# bigmuff.net
KiCad netlist of a schematic drawn in EAGLE
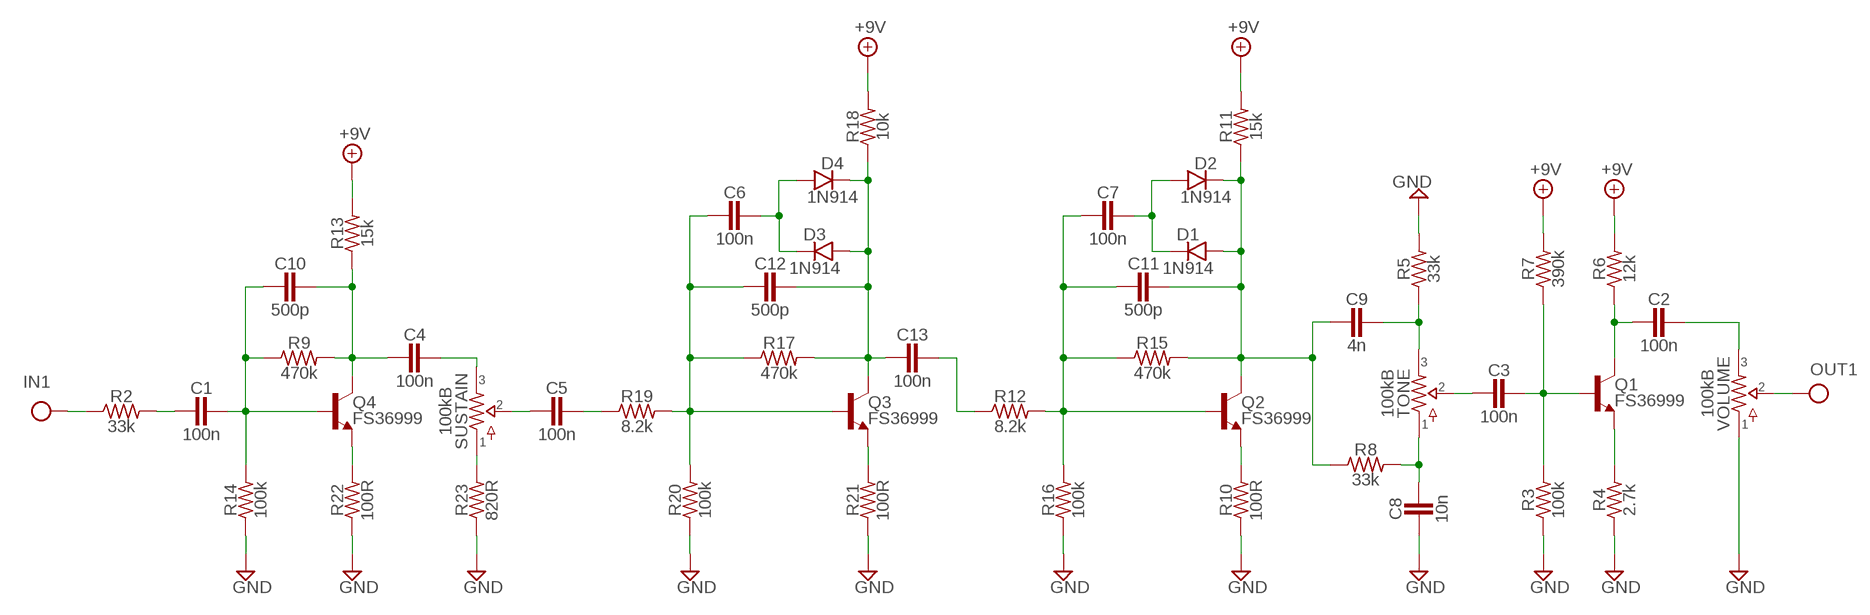
[diagram p0: schematic, sheet 1]

(export (version "E")
  (design (tool "Eeschema 10.0.6"))
  (components
    (comp (ref "C1")
      (value "100n")
      (footprint "eagle-import:BOX_SMALL")
      (libsource (lib "eagle-import") (part "CER/FILMBOX.1"))
    )
    (comp (ref "C2")
      (value "100n")
      (footprint "eagle-import:BOX_SMALL")
      (libsource (lib "eagle-import") (part "CER/FILMBOX.1"))
    )
    (comp (ref "C3")
      (value "100n")
      (footprint "eagle-import:BOX_SMALL")
      (libsource (lib "eagle-import") (part "CER/FILMBOX.1"))
    )
    (comp (ref "C4")
      (value "100n")
      (footprint "eagle-import:BOX_SMALL")
      (libsource (lib "eagle-import") (part "CER/FILMBOX.1"))
    )
    (comp (ref "C5")
      (value "100n")
      (footprint "eagle-import:BOX_SMALL")
      (libsource (lib "eagle-import") (part "CER/FILMBOX.1"))
    )
    (comp (ref "C6")
      (value "100n")
      (footprint "eagle-import:BOX_SMALL")
      (libsource (lib "eagle-import") (part "CER/FILMBOX.1"))
    )
    (comp (ref "C7")
      (value "100n")
      (footprint "eagle-import:BOX_SMALL")
      (libsource (lib "eagle-import") (part "CER/FILMBOX.1"))
    )
    (comp (ref "C8")
      (value "10n")
      (footprint "eagle-import:BOX_SMALL")
      (libsource (lib "eagle-import") (part "CER/FILMBOX.1"))
    )
    (comp (ref "C9")
      (value "4n")
      (footprint "eagle-import:BOX_SMALL")
      (libsource (lib "eagle-import") (part "CER/FILMBOX.1"))
    )
    (comp (ref "C10")
      (value "500p")
      (footprint "eagle-import:BOX_SMALL")
      (libsource (lib "eagle-import") (part "CER/FILMBOX.1"))
    )
    (comp (ref "C11")
      (value "500p")
      (footprint "eagle-import:BOX_SMALL")
      (libsource (lib "eagle-import") (part "CER/FILMBOX.1"))
    )
    (comp (ref "C12")
      (value "500p")
      (footprint "eagle-import:BOX_SMALL")
      (libsource (lib "eagle-import") (part "CER/FILMBOX.1"))
    )
    (comp (ref "C13")
      (value "100n")
      (footprint "eagle-import:BOX_SMALL")
      (libsource (lib "eagle-import") (part "CER/FILMBOX.1"))
    )
    (comp (ref "D1")
      (value "1N914")
      (footprint "eagle-import:DO41-2")
      (libsource (lib "eagle-import") (part "DO41.2"))
    )
    (comp (ref "D2")
      (value "1N914")
      (footprint "eagle-import:DO41-2")
      (libsource (lib "eagle-import") (part "DO41.2"))
    )
    (comp (ref "D3")
      (value "1N914")
      (footprint "eagle-import:DO41-2")
      (libsource (lib "eagle-import") (part "DO41.2"))
    )
    (comp (ref "D4")
      (value "1N914")
      (footprint "eagle-import:DO41-2")
      (libsource (lib "eagle-import") (part "DO41.2"))
    )
    (comp (ref "Q1")
      (value "FS36999")
      (footprint "eagle-import:TO92-")
      (libsource (lib "eagle-import") (part "2N5088"))
    )
    (comp (ref "Q2")
      (value "FS36999")
      (footprint "eagle-import:TO92-")
      (libsource (lib "eagle-import") (part "2N5088"))
    )
    (comp (ref "Q3")
      (value "FS36999")
      (footprint "eagle-import:TO92-")
      (libsource (lib "eagle-import") (part "2N5088"))
    )
    (comp (ref "Q4")
      (value "FS36999")
      (footprint "eagle-import:TO92-")
      (libsource (lib "eagle-import") (part "2N5088"))
    )
    (comp (ref "R2")
      (value "33k")
      (footprint "eagle-import:R0207_3")
      (libsource (lib "eagle-import") (part "R_.3B"))
    )
    (comp (ref "R3")
      (value "100k")
      (footprint "eagle-import:R0207_3")
      (libsource (lib "eagle-import") (part "R_.3B"))
    )
    (comp (ref "R4")
      (value "2.7k")
      (footprint "eagle-import:R0207_3")
      (libsource (lib "eagle-import") (part "R_.3B"))
    )
    (comp (ref "R5")
      (value "33k")
      (footprint "eagle-import:R0207_3")
      (libsource (lib "eagle-import") (part "R_.3B"))
    )
    (comp (ref "R6")
      (value "12k")
      (footprint "eagle-import:R0207_3")
      (libsource (lib "eagle-import") (part "R_.3B"))
    )
    (comp (ref "R7")
      (value "390k")
      (footprint "eagle-import:R0207_3")
      (libsource (lib "eagle-import") (part "R_.3B"))
    )
    (comp (ref "R8")
      (value "33k")
      (footprint "eagle-import:R0207_3")
      (libsource (lib "eagle-import") (part "R_.3B"))
    )
    (comp (ref "R9")
      (value "470k")
      (footprint "eagle-import:R0207_3")
      (libsource (lib "eagle-import") (part "R_.3B"))
    )
    (comp (ref "R10")
      (value "100R")
      (footprint "eagle-import:R0207_3")
      (libsource (lib "eagle-import") (part "R_.3B"))
    )
    (comp (ref "R11")
      (value "15k")
      (footprint "eagle-import:R0207_3")
      (libsource (lib "eagle-import") (part "R_.3B"))
    )
    (comp (ref "R12")
      (value "8.2k")
      (footprint "eagle-import:R0207_3")
      (libsource (lib "eagle-import") (part "R_.3B"))
    )
    (comp (ref "R13")
      (value "15k")
      (footprint "eagle-import:R0207_3")
      (libsource (lib "eagle-import") (part "R_.3B"))
    )
    (comp (ref "R14")
      (value "100k")
      (footprint "eagle-import:R0207_3")
      (libsource (lib "eagle-import") (part "R_.3B"))
    )
    (comp (ref "R15")
      (value "470k")
      (footprint "eagle-import:R0207_3")
      (libsource (lib "eagle-import") (part "R_.3B"))
    )
    (comp (ref "R16")
      (value "100k")
      (footprint "eagle-import:R0207_3")
      (libsource (lib "eagle-import") (part "R_.3B"))
    )
    (comp (ref "R17")
      (value "470k")
      (footprint "eagle-import:R0207_3")
      (libsource (lib "eagle-import") (part "R_.3B"))
    )
    (comp (ref "R18")
      (value "10k")
      (footprint "eagle-import:R0207_3")
      (libsource (lib "eagle-import") (part "R_.3B"))
    )
    (comp (ref "R19")
      (value "8.2k")
      (footprint "eagle-import:R0207_3")
      (libsource (lib "eagle-import") (part "R_.3B"))
    )
    (comp (ref "R20")
      (value "100k")
      (footprint "eagle-import:R0207_3")
      (libsource (lib "eagle-import") (part "R_.3B"))
    )
    (comp (ref "R21")
      (value "100R")
      (footprint "eagle-import:R0207_3")
      (libsource (lib "eagle-import") (part "R_.3B"))
    )
    (comp (ref "R22")
      (value "100R")
      (footprint "eagle-import:R0207_3")
      (libsource (lib "eagle-import") (part "R_.3B"))
    )
    (comp (ref "R23")
      (value "820R")
      (footprint "eagle-import:R0207_3")
      (libsource (lib "eagle-import") (part "R_.3B"))
    )
    (comp (ref "SUSTAIN")
      (value "100kB")
      (footprint "eagle-import:16MM")
      (libsource (lib "eagle-import") (part "POTS16MM"))
    )
    (comp (ref "TONE")
      (value "100kB")
      (footprint "eagle-import:16MM")
      (libsource (lib "eagle-import") (part "POTS16MM"))
    )
    (comp (ref "VOLUME")
      (value "100kB")
      (footprint "eagle-import:16MM")
      (libsource (lib "eagle-import") (part "POTS16MM"))
    )
  )
  (nets
    (net (code "1") (name "+9V") (class "Default")
      (node (ref "R11") (pin "2") (pinfunction "2_2") (pintype "passive"))
      (node (ref "R13") (pin "2") (pinfunction "2_2") (pintype "passive"))
      (node (ref "R18") (pin "2") (pinfunction "2_2") (pintype "passive"))
      (node (ref "R6") (pin "2") (pinfunction "2_2") (pintype "passive"))
      (node (ref "R7") (pin "2") (pinfunction "2_2") (pintype "passive"))
    )
    (net (code "2") (name "GND") (class "Default")
      (node (ref "C8") (pin "2") (pinfunction "2_2") (pintype "passive"))
      (node (ref "R10") (pin "1") (pinfunction "1_1") (pintype "passive"))
      (node (ref "R14") (pin "1") (pinfunction "1_1") (pintype "passive"))
      (node (ref "R16") (pin "1") (pinfunction "1_1") (pintype "passive"))
      (node (ref "R20") (pin "1") (pinfunction "1_1") (pintype "passive"))
      (node (ref "R21") (pin "1") (pinfunction "1_1") (pintype "passive"))
      (node (ref "R22") (pin "1") (pinfunction "1_1") (pintype "passive"))
      (node (ref "R23") (pin "1") (pinfunction "1_1") (pintype "passive"))
      (node (ref "R3") (pin "1") (pinfunction "1_1") (pintype "passive"))
      (node (ref "R4") (pin "1") (pinfunction "1_1") (pintype "passive"))
      (node (ref "R5") (pin "2") (pinfunction "2_2") (pintype "passive"))
      (node (ref "VOLUME") (pin "1") (pinfunction "1_1") (pintype "passive"))
    )
    (net (code "3") (name "IN") (class "Default")
      (node (ref "R2") (pin "1") (pinfunction "1_1") (pintype "passive"))
    )
    (net (code "4") (name "Net-(C1-Pad2)") (class "Default")
      (node (ref "C1") (pin "2") (pinfunction "2_2") (pintype "passive"))
      (node (ref "R2") (pin "2") (pinfunction "2_2") (pintype "passive"))
    )
    (net (code "5") (name "Net-(C2-Pad1)") (class "Default")
      (node (ref "C2") (pin "1") (pinfunction "1_1") (pintype "passive"))
      (node (ref "VOLUME") (pin "3") (pinfunction "3_3") (pintype "passive"))
    )
    (net (code "6") (name "Net-(C3-Pad2)") (class "Default")
      (node (ref "C3") (pin "2") (pinfunction "2_2") (pintype "passive"))
      (node (ref "TONE") (pin "2") (pinfunction "2_2") (pintype "passive"))
    )
    (net (code "7") (name "Net-(C4-Pad1)") (class "Default")
      (node (ref "C4") (pin "1") (pinfunction "1_1") (pintype "passive"))
      (node (ref "SUSTAIN") (pin "3") (pinfunction "3_3") (pintype "passive"))
    )
    (net (code "8") (name "Net-(C5-Pad1)") (class "Default")
      (node (ref "C5") (pin "1") (pinfunction "1_1") (pintype "passive"))
      (node (ref "R19") (pin "1") (pinfunction "1_1") (pintype "passive"))
    )
    (net (code "9") (name "Net-(C5-Pad2)") (class "Default")
      (node (ref "C5") (pin "2") (pinfunction "2_2") (pintype "passive"))
      (node (ref "SUSTAIN") (pin "2") (pinfunction "2_2") (pintype "passive"))
    )
    (net (code "10") (name "Net-(C6-Pad1)") (class "Default")
      (node (ref "C6") (pin "1") (pinfunction "1_1") (pintype "passive"))
      (node (ref "D3") (pin "C") (pinfunction "C_C") (pintype "passive"))
      (node (ref "D4") (pin "A") (pinfunction "A_A") (pintype "passive"))
    )
    (net (code "11") (name "Net-(C7-Pad1)") (class "Default")
      (node (ref "C7") (pin "1") (pinfunction "1_1") (pintype "passive"))
      (node (ref "D1") (pin "C") (pinfunction "C_C") (pintype "passive"))
      (node (ref "D2") (pin "A") (pinfunction "A_A") (pintype "passive"))
    )
    (net (code "12") (name "Net-(C8-Pad1)") (class "Default")
      (node (ref "C8") (pin "1") (pinfunction "1_1") (pintype "passive"))
      (node (ref "R8") (pin "2") (pinfunction "2_2") (pintype "passive"))
      (node (ref "TONE") (pin "1") (pinfunction "1_1") (pintype "passive"))
    )
    (net (code "13") (name "Net-(C9-Pad1)") (class "Default")
      (node (ref "C9") (pin "1") (pinfunction "1_1") (pintype "passive"))
      (node (ref "R5") (pin "1") (pinfunction "1_1") (pintype "passive"))
      (node (ref "TONE") (pin "3") (pinfunction "3_3") (pintype "passive"))
    )
    (net (code "14") (name "Net-(C13-Pad1)") (class "Default")
      (node (ref "C13") (pin "1") (pinfunction "1_1") (pintype "passive"))
      (node (ref "R12") (pin "1") (pinfunction "1_1") (pintype "passive"))
    )
    (net (code "15") (name "Net-(Q1-B)") (class "Default")
      (node (ref "C3") (pin "1") (pinfunction "1_1") (pintype "passive"))
      (node (ref "Q1") (pin "2") (pinfunction "B_2") (pintype "passive"))
      (node (ref "R3") (pin "2") (pinfunction "2_2") (pintype "passive"))
      (node (ref "R7") (pin "1") (pinfunction "1_1") (pintype "passive"))
    )
    (net (code "16") (name "Net-(Q1-C)") (class "Default")
      (node (ref "C2") (pin "2") (pinfunction "2_2") (pintype "passive"))
      (node (ref "Q1") (pin "1") (pinfunction "C_1") (pintype "passive"))
      (node (ref "R6") (pin "1") (pinfunction "1_1") (pintype "passive"))
    )
    (net (code "17") (name "Net-(Q1-E)") (class "Default")
      (node (ref "Q1") (pin "3") (pinfunction "E_3") (pintype "passive"))
      (node (ref "R4") (pin "2") (pinfunction "2_2") (pintype "passive"))
    )
    (net (code "18") (name "Net-(Q2-B)") (class "Default")
      (node (ref "C11") (pin "2") (pinfunction "2_2") (pintype "passive"))
      (node (ref "C7") (pin "2") (pinfunction "2_2") (pintype "passive"))
      (node (ref "Q2") (pin "2") (pinfunction "B_2") (pintype "passive"))
      (node (ref "R12") (pin "2") (pinfunction "2_2") (pintype "passive"))
      (node (ref "R15") (pin "1") (pinfunction "1_1") (pintype "passive"))
      (node (ref "R16") (pin "2") (pinfunction "2_2") (pintype "passive"))
    )
    (net (code "19") (name "Net-(Q2-C)") (class "Default")
      (node (ref "C11") (pin "1") (pinfunction "1_1") (pintype "passive"))
      (node (ref "C9") (pin "2") (pinfunction "2_2") (pintype "passive"))
      (node (ref "D1") (pin "A") (pinfunction "A_A") (pintype "passive"))
      (node (ref "D2") (pin "C") (pinfunction "C_C") (pintype "passive"))
      (node (ref "Q2") (pin "1") (pinfunction "C_1") (pintype "passive"))
      (node (ref "R11") (pin "1") (pinfunction "1_1") (pintype "passive"))
      (node (ref "R15") (pin "2") (pinfunction "2_2") (pintype "passive"))
      (node (ref "R8") (pin "1") (pinfunction "1_1") (pintype "passive"))
    )
    (net (code "20") (name "Net-(Q2-E)") (class "Default")
      (node (ref "Q2") (pin "3") (pinfunction "E_3") (pintype "passive"))
      (node (ref "R10") (pin "2") (pinfunction "2_2") (pintype "passive"))
    )
    (net (code "21") (name "Net-(Q3-B)") (class "Default")
      (node (ref "C12") (pin "2") (pinfunction "2_2") (pintype "passive"))
      (node (ref "C6") (pin "2") (pinfunction "2_2") (pintype "passive"))
      (node (ref "Q3") (pin "2") (pinfunction "B_2") (pintype "passive"))
      (node (ref "R17") (pin "1") (pinfunction "1_1") (pintype "passive"))
      (node (ref "R19") (pin "2") (pinfunction "2_2") (pintype "passive"))
      (node (ref "R20") (pin "2") (pinfunction "2_2") (pintype "passive"))
    )
    (net (code "22") (name "Net-(Q3-C)") (class "Default")
      (node (ref "C12") (pin "1") (pinfunction "1_1") (pintype "passive"))
      (node (ref "C13") (pin "2") (pinfunction "2_2") (pintype "passive"))
      (node (ref "D3") (pin "A") (pinfunction "A_A") (pintype "passive"))
      (node (ref "D4") (pin "C") (pinfunction "C_C") (pintype "passive"))
      (node (ref "Q3") (pin "1") (pinfunction "C_1") (pintype "passive"))
      (node (ref "R17") (pin "2") (pinfunction "2_2") (pintype "passive"))
      (node (ref "R18") (pin "1") (pinfunction "1_1") (pintype "passive"))
    )
    (net (code "23") (name "Net-(Q3-E)") (class "Default")
      (node (ref "Q3") (pin "3") (pinfunction "E_3") (pintype "passive"))
      (node (ref "R21") (pin "2") (pinfunction "2_2") (pintype "passive"))
    )
    (net (code "24") (name "Net-(Q4-B)") (class "Default")
      (node (ref "C1") (pin "1") (pinfunction "1_1") (pintype "passive"))
      (node (ref "C10") (pin "2") (pinfunction "2_2") (pintype "passive"))
      (node (ref "Q4") (pin "2") (pinfunction "B_2") (pintype "passive"))
      (node (ref "R14") (pin "2") (pinfunction "2_2") (pintype "passive"))
      (node (ref "R9") (pin "1") (pinfunction "1_1") (pintype "passive"))
    )
    (net (code "25") (name "Net-(Q4-C)") (class "Default")
      (node (ref "C10") (pin "1") (pinfunction "1_1") (pintype "passive"))
      (node (ref "C4") (pin "2") (pinfunction "2_2") (pintype "passive"))
      (node (ref "Q4") (pin "1") (pinfunction "C_1") (pintype "passive"))
      (node (ref "R13") (pin "1") (pinfunction "1_1") (pintype "passive"))
      (node (ref "R9") (pin "2") (pinfunction "2_2") (pintype "passive"))
    )
    (net (code "26") (name "Net-(Q4-E)") (class "Default")
      (node (ref "Q4") (pin "3") (pinfunction "E_3") (pintype "passive"))
      (node (ref "R22") (pin "2") (pinfunction "2_2") (pintype "passive"))
    )
    (net (code "27") (name "Net-(R23-Pad2)") (class "Default")
      (node (ref "R23") (pin "2") (pinfunction "2_2") (pintype "passive"))
      (node (ref "SUSTAIN") (pin "1") (pinfunction "1_1") (pintype "passive"))
    )
    (net (code "28") (name "OUT") (class "Default")
      (node (ref "VOLUME") (pin "2") (pinfunction "2_2") (pintype "passive"))
    )
  )
)
